# DR_EIB-128_MillMax_NewParts.net
KiCad netlist of a schematic drawn in EAGLE
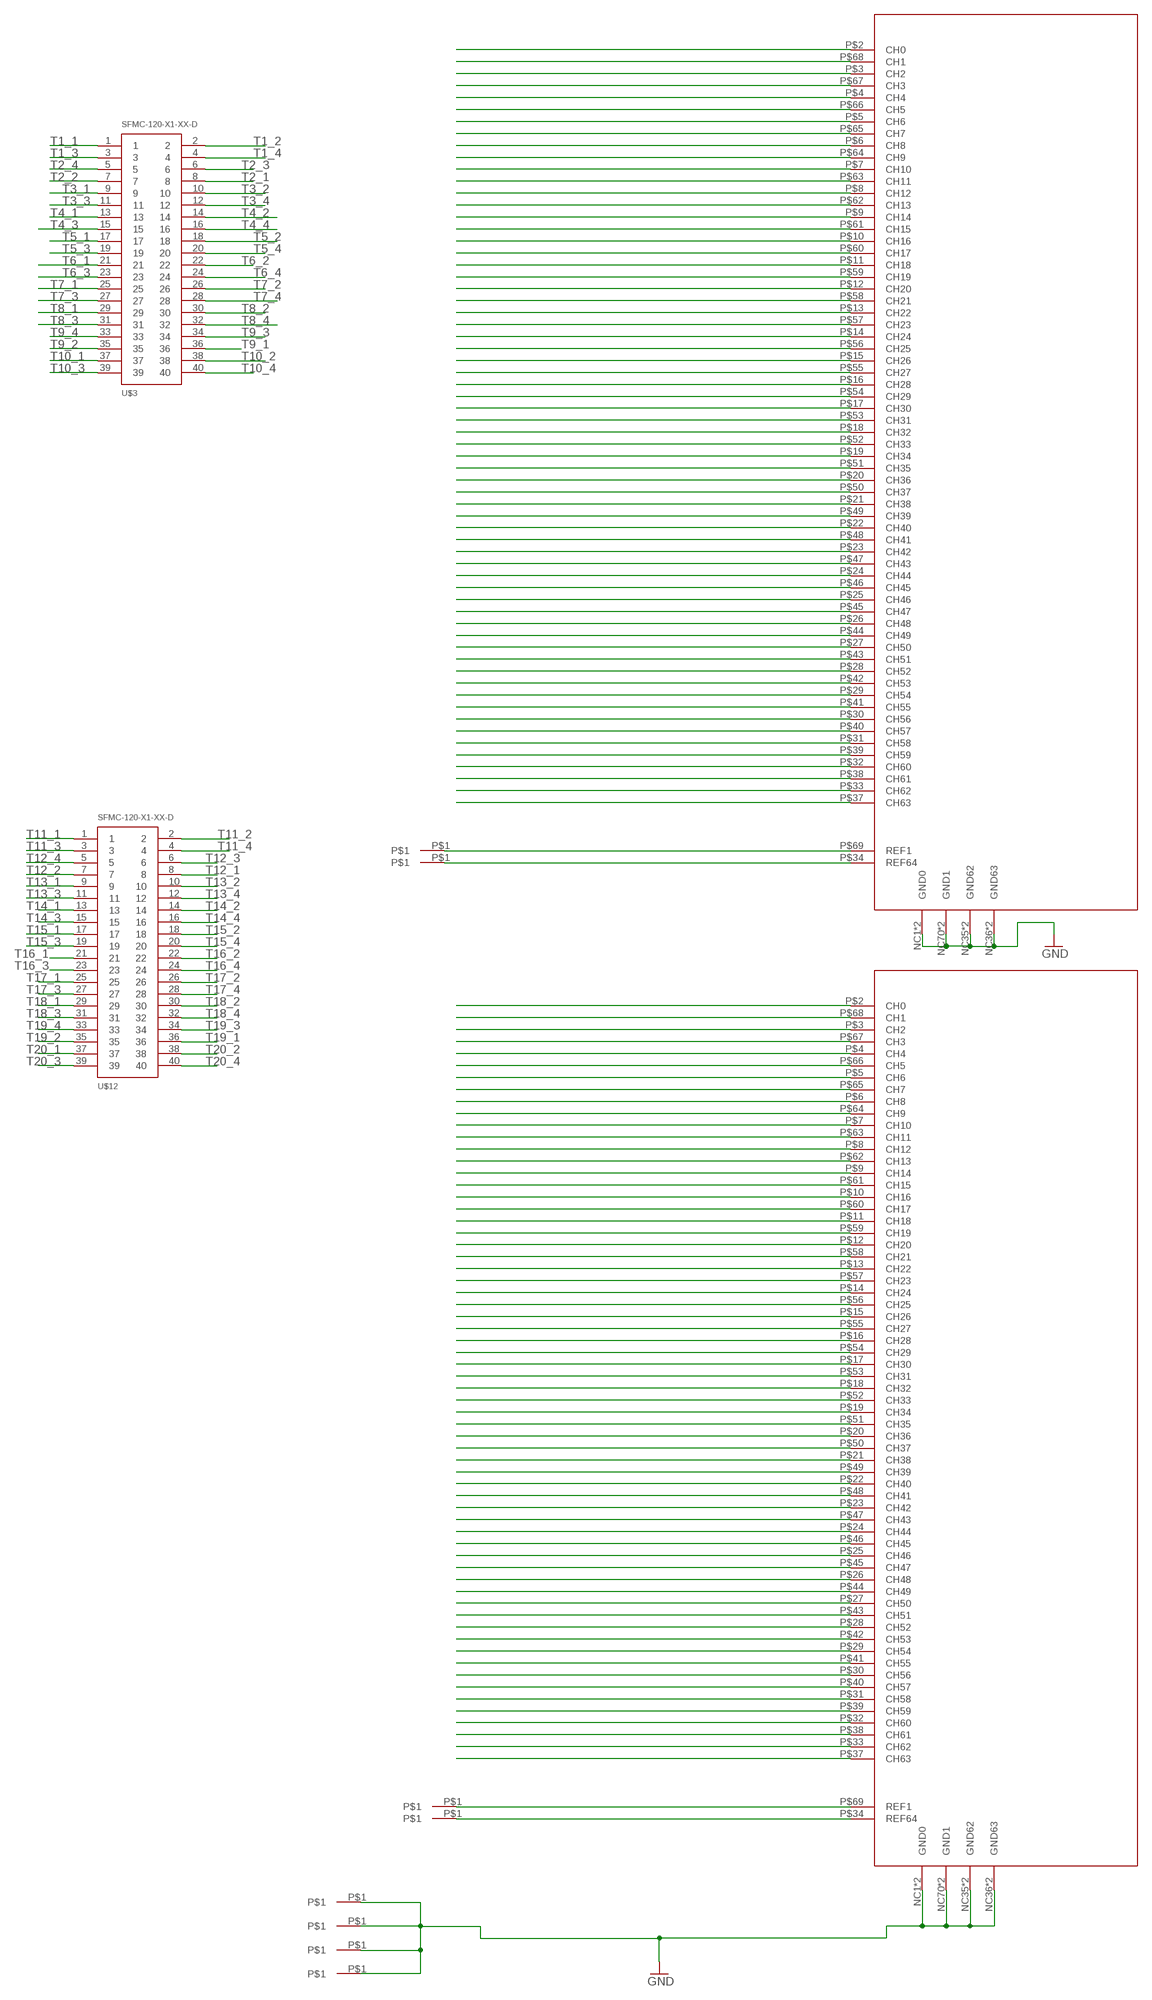
[diagram p0: schematic, sheet 1]

(export (version "E")
  (design (tool "Eeschema 10.0.6"))
  (components
    (comp (ref "U$1")
      (value "TARRAYSHUTTLEHOLE")
      (footprint "eagle-import:TARRAYSHUTTLEHOLE")
      (libsource (lib "eagle-import") (part "TARRAYSHUTTLEHOLE"))
    )
    (comp (ref "U$2")
      (value "TARRAYSHUTTLEHOLE")
      (footprint "eagle-import:TARRAYSHUTTLEHOLE")
      (libsource (lib "eagle-import") (part "TARRAYSHUTTLEHOLE"))
    )
    (comp (ref "U$3")
      (value "SFMC-120-X1-XX-D")
      (footprint "eagle-import:SFMC-120-X1-XX-D")
      (libsource (lib "eagle-import") (part "SFMC-120-X1-XX-D"))
    )
    (comp (ref "U$4")
      (value "TARRAYSHUTTLEHOLE")
      (footprint "eagle-import:TARRAYSHUTTLEHOLE")
      (libsource (lib "eagle-import") (part "TARRAYSHUTTLEHOLE"))
    )
    (comp (ref "U$5")
      (value "TARRAYSHUTTLEHOLE")
      (footprint "eagle-import:TARRAYSHUTTLEHOLE")
      (libsource (lib "eagle-import") (part "TARRAYSHUTTLEHOLE"))
    )
    (comp (ref "U$6")
      (value "TARRAYSHUTTLEHOLE")
      (footprint "eagle-import:TARRAYSHUTTLEHOLE")
      (libsource (lib "eagle-import") (part "TARRAYSHUTTLEHOLE"))
    )
    (comp (ref "U$7")
      (value "TARRAYSHUTTLEHOLE")
      (footprint "eagle-import:TARRAYSHUTTLEHOLE")
      (libsource (lib "eagle-import") (part "TARRAYSHUTTLEHOLE"))
    )
    (comp (ref "U$8")
      (value "TARRAYSHUTTLEHOLE")
      (footprint "eagle-import:TARRAYSHUTTLEHOLE")
      (libsource (lib "eagle-import") (part "TARRAYSHUTTLEHOLE"))
    )
    (comp (ref "U$9")
      (value "TARRAYSHUTTLEHOLE")
      (footprint "eagle-import:TARRAYSHUTTLEHOLE")
      (libsource (lib "eagle-import") (part "TARRAYSHUTTLEHOLE"))
    )
    (comp (ref "U$10")
      (value "HIROSE-70PIN-HEADER")
      (footprint "eagle-import:DF40C-70DP-0.4V")
      (libsource (lib "eagle-import") (part "HIROSE-70PIN-HEADER"))
    )
    (comp (ref "U$11")
      (value "HIROSE-70PIN-HEADER")
      (footprint "eagle-import:DF40C-70DP-0.4V")
      (libsource (lib "eagle-import") (part "HIROSE-70PIN-HEADER"))
    )
    (comp (ref "U$12")
      (value "SFMC-120-X1-XX-D")
      (footprint "eagle-import:SFMC-120-X1-XX-D")
      (libsource (lib "eagle-import") (part "SFMC-120-X1-XX-D"))
    )
  )
  (nets
    (net (code "1") (name "/T1_1") (class "Default")
      (node (ref "U$10") (pin "P$37") (pinfunction "CH63_P$37") (pintype "input"))
      (node (ref "U$3") (pin "1") (pinfunction "1_1") (pintype "bidirectional"))
    )
    (net (code "2") (name "/T1_2") (class "Default")
      (node (ref "U$10") (pin "P$38") (pinfunction "CH61_P$38") (pintype "input"))
      (node (ref "U$3") (pin "2") (pinfunction "2_2") (pintype "bidirectional"))
    )
    (net (code "3") (name "/T1_3") (class "Default")
      (node (ref "U$10") (pin "P$39") (pinfunction "CH59_P$39") (pintype "input"))
      (node (ref "U$3") (pin "3") (pinfunction "3_3") (pintype "bidirectional"))
    )
    (net (code "4") (name "/T1_4") (class "Default")
      (node (ref "U$10") (pin "P$40") (pinfunction "CH57_P$40") (pintype "input"))
      (node (ref "U$3") (pin "4") (pinfunction "4_4") (pintype "bidirectional"))
    )
    (net (code "5") (name "/T2_1") (class "Default")
      (node (ref "U$10") (pin "P$30") (pinfunction "CH56_P$30") (pintype "input"))
      (node (ref "U$3") (pin "8") (pinfunction "8_8") (pintype "bidirectional"))
    )
    (net (code "6") (name "/T2_2") (class "Default")
      (node (ref "U$10") (pin "P$31") (pinfunction "CH58_P$31") (pintype "input"))
      (node (ref "U$3") (pin "7") (pinfunction "7_7") (pintype "bidirectional"))
    )
    (net (code "7") (name "/T2_3") (class "Default")
      (node (ref "U$10") (pin "P$32") (pinfunction "CH60_P$32") (pintype "input"))
      (node (ref "U$3") (pin "6") (pinfunction "6_6") (pintype "bidirectional"))
    )
    (net (code "8") (name "/T2_4") (class "Default")
      (node (ref "U$10") (pin "P$33") (pinfunction "CH62_P$33") (pintype "input"))
      (node (ref "U$3") (pin "5") (pinfunction "5_5") (pintype "bidirectional"))
    )
    (net (code "9") (name "/T3_1") (class "Default")
      (node (ref "U$10") (pin "P$29") (pinfunction "CH54_P$29") (pintype "input"))
      (node (ref "U$3") (pin "9") (pinfunction "9_9") (pintype "bidirectional"))
    )
    (net (code "10") (name "/T3_2") (class "Default")
      (node (ref "U$10") (pin "P$28") (pinfunction "CH52_P$28") (pintype "input"))
      (node (ref "U$3") (pin "10") (pinfunction "10_10") (pintype "bidirectional"))
    )
    (net (code "11") (name "/T3_3") (class "Default")
      (node (ref "U$10") (pin "P$27") (pinfunction "CH50_P$27") (pintype "input"))
      (node (ref "U$3") (pin "11") (pinfunction "11_11") (pintype "bidirectional"))
    )
    (net (code "12") (name "/T3_4") (class "Default")
      (node (ref "U$10") (pin "P$26") (pinfunction "CH48_P$26") (pintype "input"))
      (node (ref "U$3") (pin "12") (pinfunction "12_12") (pintype "bidirectional"))
    )
    (net (code "13") (name "/T4_1") (class "Default")
      (node (ref "U$10") (pin "P$25") (pinfunction "CH46_P$25") (pintype "input"))
      (node (ref "U$3") (pin "13") (pinfunction "13_13") (pintype "bidirectional"))
    )
    (net (code "14") (name "/T4_2") (class "Default")
      (node (ref "U$10") (pin "P$24") (pinfunction "CH44_P$24") (pintype "input"))
      (node (ref "U$3") (pin "14") (pinfunction "14_14") (pintype "bidirectional"))
    )
    (net (code "15") (name "/T4_3") (class "Default")
      (node (ref "U$10") (pin "P$23") (pinfunction "CH42_P$23") (pintype "input"))
      (node (ref "U$3") (pin "15") (pinfunction "15_15") (pintype "bidirectional"))
    )
    (net (code "16") (name "/T4_4") (class "Default")
      (node (ref "U$10") (pin "P$22") (pinfunction "CH40_P$22") (pintype "input"))
      (node (ref "U$3") (pin "16") (pinfunction "16_16") (pintype "bidirectional"))
    )
    (net (code "17") (name "/T5_1") (class "Default")
      (node (ref "U$10") (pin "P$21") (pinfunction "CH38_P$21") (pintype "input"))
      (node (ref "U$3") (pin "17") (pinfunction "17_17") (pintype "bidirectional"))
    )
    (net (code "18") (name "/T5_2") (class "Default")
      (node (ref "U$10") (pin "P$20") (pinfunction "CH36_P$20") (pintype "input"))
      (node (ref "U$3") (pin "18") (pinfunction "18_18") (pintype "bidirectional"))
    )
    (net (code "19") (name "/T5_3") (class "Default")
      (node (ref "U$10") (pin "P$19") (pinfunction "CH34_P$19") (pintype "input"))
      (node (ref "U$3") (pin "19") (pinfunction "19_19") (pintype "bidirectional"))
    )
    (net (code "20") (name "/T5_4") (class "Default")
      (node (ref "U$10") (pin "P$18") (pinfunction "CH32_P$18") (pintype "input"))
      (node (ref "U$3") (pin "20") (pinfunction "20_20") (pintype "bidirectional"))
    )
    (net (code "21") (name "/T6_1") (class "Default")
      (node (ref "U$11") (pin "P$17") (pinfunction "CH30_P$17") (pintype "input"))
      (node (ref "U$3") (pin "21") (pinfunction "21_21") (pintype "bidirectional"))
    )
    (net (code "22") (name "/T6_2") (class "Default")
      (node (ref "U$11") (pin "P$16") (pinfunction "CH28_P$16") (pintype "input"))
      (node (ref "U$3") (pin "22") (pinfunction "22_22") (pintype "bidirectional"))
    )
    (net (code "23") (name "/T6_3") (class "Default")
      (node (ref "U$11") (pin "P$15") (pinfunction "CH26_P$15") (pintype "input"))
      (node (ref "U$3") (pin "23") (pinfunction "23_23") (pintype "bidirectional"))
    )
    (net (code "24") (name "/T6_4") (class "Default")
      (node (ref "U$11") (pin "P$14") (pinfunction "CH24_P$14") (pintype "input"))
      (node (ref "U$3") (pin "24") (pinfunction "24_24") (pintype "bidirectional"))
    )
    (net (code "25") (name "/T7_1") (class "Default")
      (node (ref "U$11") (pin "P$13") (pinfunction "CH22_P$13") (pintype "input"))
      (node (ref "U$3") (pin "25") (pinfunction "25_25") (pintype "bidirectional"))
    )
    (net (code "26") (name "/T7_2") (class "Default")
      (node (ref "U$11") (pin "P$12") (pinfunction "CH20_P$12") (pintype "input"))
      (node (ref "U$3") (pin "26") (pinfunction "26_26") (pintype "bidirectional"))
    )
    (net (code "27") (name "/T7_3") (class "Default")
      (node (ref "U$11") (pin "P$11") (pinfunction "CH18_P$11") (pintype "input"))
      (node (ref "U$3") (pin "27") (pinfunction "27_27") (pintype "bidirectional"))
    )
    (net (code "28") (name "/T7_4") (class "Default")
      (node (ref "U$11") (pin "P$10") (pinfunction "CH16_P$10") (pintype "input"))
      (node (ref "U$3") (pin "28") (pinfunction "28_28") (pintype "bidirectional"))
    )
    (net (code "29") (name "/T8_1") (class "Default")
      (node (ref "U$11") (pin "P$9") (pinfunction "CH14_P$9") (pintype "input"))
      (node (ref "U$3") (pin "29") (pinfunction "29_29") (pintype "bidirectional"))
    )
    (net (code "30") (name "/T8_2") (class "Default")
      (node (ref "U$11") (pin "P$8") (pinfunction "CH12_P$8") (pintype "input"))
      (node (ref "U$3") (pin "30") (pinfunction "30_30") (pintype "bidirectional"))
    )
    (net (code "31") (name "/T8_3") (class "Default")
      (node (ref "U$11") (pin "P$7") (pinfunction "CH10_P$7") (pintype "input"))
      (node (ref "U$3") (pin "31") (pinfunction "31_31") (pintype "bidirectional"))
    )
    (net (code "32") (name "/T8_4") (class "Default")
      (node (ref "U$11") (pin "P$6") (pinfunction "CH8_P$6") (pintype "input"))
      (node (ref "U$3") (pin "32") (pinfunction "32_32") (pintype "bidirectional"))
    )
    (net (code "33") (name "/T9_1") (class "Default")
      (node (ref "U$11") (pin "P$2") (pinfunction "CH0_P$2") (pintype "input"))
      (node (ref "U$3") (pin "36") (pinfunction "36_36") (pintype "bidirectional"))
    )
    (net (code "34") (name "/T9_2") (class "Default")
      (node (ref "U$11") (pin "P$3") (pinfunction "CH2_P$3") (pintype "input"))
      (node (ref "U$3") (pin "35") (pinfunction "35_35") (pintype "bidirectional"))
    )
    (net (code "35") (name "/T9_3") (class "Default")
      (node (ref "U$11") (pin "P$4") (pinfunction "CH4_P$4") (pintype "input"))
      (node (ref "U$3") (pin "34") (pinfunction "34_34") (pintype "bidirectional"))
    )
    (net (code "36") (name "/T9_4") (class "Default")
      (node (ref "U$11") (pin "P$5") (pinfunction "CH6_P$5") (pintype "input"))
      (node (ref "U$3") (pin "33") (pinfunction "33_33") (pintype "bidirectional"))
    )
    (net (code "37") (name "/T10_1") (class "Default")
      (node (ref "U$11") (pin "P$65") (pinfunction "CH7_P$65") (pintype "input"))
      (node (ref "U$3") (pin "37") (pinfunction "37_37") (pintype "bidirectional"))
    )
    (net (code "38") (name "/T10_2") (class "Default")
      (node (ref "U$11") (pin "P$66") (pinfunction "CH5_P$66") (pintype "input"))
      (node (ref "U$3") (pin "38") (pinfunction "38_38") (pintype "bidirectional"))
    )
    (net (code "39") (name "/T10_3") (class "Default")
      (node (ref "U$11") (pin "P$67") (pinfunction "CH3_P$67") (pintype "input"))
      (node (ref "U$3") (pin "39") (pinfunction "39_39") (pintype "bidirectional"))
    )
    (net (code "40") (name "/T10_4") (class "Default")
      (node (ref "U$11") (pin "P$68") (pinfunction "CH1_P$68") (pintype "input"))
      (node (ref "U$3") (pin "40") (pinfunction "40_40") (pintype "bidirectional"))
    )
    (net (code "41") (name "/T11_1") (class "Default")
      (node (ref "U$11") (pin "P$37") (pinfunction "CH63_P$37") (pintype "input"))
      (node (ref "U$12") (pin "1") (pinfunction "1_1") (pintype "bidirectional"))
    )
    (net (code "42") (name "/T11_2") (class "Default")
      (node (ref "U$11") (pin "P$38") (pinfunction "CH61_P$38") (pintype "input"))
      (node (ref "U$12") (pin "2") (pinfunction "2_2") (pintype "bidirectional"))
    )
    (net (code "43") (name "/T11_3") (class "Default")
      (node (ref "U$11") (pin "P$39") (pinfunction "CH59_P$39") (pintype "input"))
      (node (ref "U$12") (pin "3") (pinfunction "3_3") (pintype "bidirectional"))
    )
    (net (code "44") (name "/T11_4") (class "Default")
      (node (ref "U$11") (pin "P$40") (pinfunction "CH57_P$40") (pintype "input"))
      (node (ref "U$12") (pin "4") (pinfunction "4_4") (pintype "bidirectional"))
    )
    (net (code "45") (name "/T12_1") (class "Default")
      (node (ref "U$11") (pin "P$30") (pinfunction "CH56_P$30") (pintype "input"))
      (node (ref "U$12") (pin "8") (pinfunction "8_8") (pintype "bidirectional"))
    )
    (net (code "46") (name "/T12_2") (class "Default")
      (node (ref "U$11") (pin "P$31") (pinfunction "CH58_P$31") (pintype "input"))
      (node (ref "U$12") (pin "7") (pinfunction "7_7") (pintype "bidirectional"))
    )
    (net (code "47") (name "/T12_3") (class "Default")
      (node (ref "U$11") (pin "P$32") (pinfunction "CH60_P$32") (pintype "input"))
      (node (ref "U$12") (pin "6") (pinfunction "6_6") (pintype "bidirectional"))
    )
    (net (code "48") (name "/T12_4") (class "Default")
      (node (ref "U$11") (pin "P$33") (pinfunction "CH62_P$33") (pintype "input"))
      (node (ref "U$12") (pin "5") (pinfunction "5_5") (pintype "bidirectional"))
    )
    (net (code "49") (name "/T13_1") (class "Default")
      (node (ref "U$11") (pin "P$29") (pinfunction "CH54_P$29") (pintype "input"))
      (node (ref "U$12") (pin "9") (pinfunction "9_9") (pintype "bidirectional"))
    )
    (net (code "50") (name "/T13_2") (class "Default")
      (node (ref "U$11") (pin "P$28") (pinfunction "CH52_P$28") (pintype "input"))
      (node (ref "U$12") (pin "10") (pinfunction "10_10") (pintype "bidirectional"))
    )
    (net (code "51") (name "/T13_3") (class "Default")
      (node (ref "U$11") (pin "P$27") (pinfunction "CH50_P$27") (pintype "input"))
      (node (ref "U$12") (pin "11") (pinfunction "11_11") (pintype "bidirectional"))
    )
    (net (code "52") (name "/T13_4") (class "Default")
      (node (ref "U$11") (pin "P$26") (pinfunction "CH48_P$26") (pintype "input"))
      (node (ref "U$12") (pin "12") (pinfunction "12_12") (pintype "bidirectional"))
    )
    (net (code "53") (name "/T14_1") (class "Default")
      (node (ref "U$11") (pin "P$25") (pinfunction "CH46_P$25") (pintype "input"))
      (node (ref "U$12") (pin "13") (pinfunction "13_13") (pintype "bidirectional"))
    )
    (net (code "54") (name "/T14_2") (class "Default")
      (node (ref "U$11") (pin "P$24") (pinfunction "CH44_P$24") (pintype "input"))
      (node (ref "U$12") (pin "14") (pinfunction "14_14") (pintype "bidirectional"))
    )
    (net (code "55") (name "/T14_3") (class "Default")
      (node (ref "U$11") (pin "P$23") (pinfunction "CH42_P$23") (pintype "input"))
      (node (ref "U$12") (pin "15") (pinfunction "15_15") (pintype "bidirectional"))
    )
    (net (code "56") (name "/T14_4") (class "Default")
      (node (ref "U$11") (pin "P$22") (pinfunction "CH40_P$22") (pintype "input"))
      (node (ref "U$12") (pin "16") (pinfunction "16_16") (pintype "bidirectional"))
    )
    (net (code "57") (name "/T15_1") (class "Default")
      (node (ref "U$11") (pin "P$21") (pinfunction "CH38_P$21") (pintype "input"))
      (node (ref "U$12") (pin "17") (pinfunction "17_17") (pintype "bidirectional"))
    )
    (net (code "58") (name "/T15_2") (class "Default")
      (node (ref "U$11") (pin "P$20") (pinfunction "CH36_P$20") (pintype "input"))
      (node (ref "U$12") (pin "18") (pinfunction "18_18") (pintype "bidirectional"))
    )
    (net (code "59") (name "/T15_3") (class "Default")
      (node (ref "U$11") (pin "P$19") (pinfunction "CH34_P$19") (pintype "input"))
      (node (ref "U$12") (pin "19") (pinfunction "19_19") (pintype "bidirectional"))
    )
    (net (code "60") (name "/T15_4") (class "Default")
      (node (ref "U$11") (pin "P$18") (pinfunction "CH32_P$18") (pintype "input"))
      (node (ref "U$12") (pin "20") (pinfunction "20_20") (pintype "bidirectional"))
    )
    (net (code "61") (name "/T16_1") (class "Default")
      (node (ref "U$10") (pin "P$17") (pinfunction "CH30_P$17") (pintype "input"))
      (node (ref "U$12") (pin "21") (pinfunction "21_21") (pintype "bidirectional"))
    )
    (net (code "62") (name "/T16_2") (class "Default")
      (node (ref "U$10") (pin "P$16") (pinfunction "CH28_P$16") (pintype "input"))
      (node (ref "U$12") (pin "22") (pinfunction "22_22") (pintype "bidirectional"))
    )
    (net (code "63") (name "/T16_3") (class "Default")
      (node (ref "U$10") (pin "P$15") (pinfunction "CH26_P$15") (pintype "input"))
      (node (ref "U$12") (pin "23") (pinfunction "23_23") (pintype "bidirectional"))
    )
    (net (code "64") (name "/T16_4") (class "Default")
      (node (ref "U$10") (pin "P$14") (pinfunction "CH24_P$14") (pintype "input"))
      (node (ref "U$12") (pin "24") (pinfunction "24_24") (pintype "bidirectional"))
    )
    (net (code "65") (name "/T17_1") (class "Default")
      (node (ref "U$10") (pin "P$13") (pinfunction "CH22_P$13") (pintype "input"))
      (node (ref "U$12") (pin "25") (pinfunction "25_25") (pintype "bidirectional"))
    )
    (net (code "66") (name "/T17_2") (class "Default")
      (node (ref "U$10") (pin "P$12") (pinfunction "CH20_P$12") (pintype "input"))
      (node (ref "U$12") (pin "26") (pinfunction "26_26") (pintype "bidirectional"))
    )
    (net (code "67") (name "/T17_3") (class "Default")
      (node (ref "U$10") (pin "P$11") (pinfunction "CH18_P$11") (pintype "input"))
      (node (ref "U$12") (pin "27") (pinfunction "27_27") (pintype "bidirectional"))
    )
    (net (code "68") (name "/T17_4") (class "Default")
      (node (ref "U$10") (pin "P$10") (pinfunction "CH16_P$10") (pintype "input"))
      (node (ref "U$12") (pin "28") (pinfunction "28_28") (pintype "bidirectional"))
    )
    (net (code "69") (name "/T18_1") (class "Default")
      (node (ref "U$10") (pin "P$9") (pinfunction "CH14_P$9") (pintype "input"))
      (node (ref "U$12") (pin "29") (pinfunction "29_29") (pintype "bidirectional"))
    )
    (net (code "70") (name "/T18_2") (class "Default")
      (node (ref "U$10") (pin "P$8") (pinfunction "CH12_P$8") (pintype "input"))
      (node (ref "U$12") (pin "30") (pinfunction "30_30") (pintype "bidirectional"))
    )
    (net (code "71") (name "/T18_3") (class "Default")
      (node (ref "U$10") (pin "P$7") (pinfunction "CH10_P$7") (pintype "input"))
      (node (ref "U$12") (pin "31") (pinfunction "31_31") (pintype "bidirectional"))
    )
    (net (code "72") (name "/T18_4") (class "Default")
      (node (ref "U$10") (pin "P$6") (pinfunction "CH8_P$6") (pintype "input"))
      (node (ref "U$12") (pin "32") (pinfunction "32_32") (pintype "bidirectional"))
    )
    (net (code "73") (name "/T19_1") (class "Default")
      (node (ref "U$10") (pin "P$2") (pinfunction "CH0_P$2") (pintype "input"))
      (node (ref "U$12") (pin "36") (pinfunction "36_36") (pintype "bidirectional"))
    )
    (net (code "74") (name "/T19_2") (class "Default")
      (node (ref "U$10") (pin "P$3") (pinfunction "CH2_P$3") (pintype "input"))
      (node (ref "U$12") (pin "35") (pinfunction "35_35") (pintype "bidirectional"))
    )
    (net (code "75") (name "/T19_3") (class "Default")
      (node (ref "U$10") (pin "P$4") (pinfunction "CH4_P$4") (pintype "input"))
      (node (ref "U$12") (pin "34") (pinfunction "34_34") (pintype "bidirectional"))
    )
    (net (code "76") (name "/T19_4") (class "Default")
      (node (ref "U$10") (pin "P$5") (pinfunction "CH6_P$5") (pintype "input"))
      (node (ref "U$12") (pin "33") (pinfunction "33_33") (pintype "bidirectional"))
    )
    (net (code "77") (name "/T20_1") (class "Default")
      (node (ref "U$10") (pin "P$65") (pinfunction "CH7_P$65") (pintype "input"))
      (node (ref "U$12") (pin "37") (pinfunction "37_37") (pintype "bidirectional"))
    )
    (net (code "78") (name "/T20_2") (class "Default")
      (node (ref "U$10") (pin "P$66") (pinfunction "CH5_P$66") (pintype "input"))
      (node (ref "U$12") (pin "38") (pinfunction "38_38") (pintype "bidirectional"))
    )
    (net (code "79") (name "/T20_3") (class "Default")
      (node (ref "U$10") (pin "P$67") (pinfunction "CH3_P$67") (pintype "input"))
      (node (ref "U$12") (pin "39") (pinfunction "39_39") (pintype "bidirectional"))
    )
    (net (code "80") (name "/T20_4") (class "Default")
      (node (ref "U$10") (pin "P$68") (pinfunction "CH1_P$68") (pintype "input"))
      (node (ref "U$12") (pin "40") (pinfunction "40_40") (pintype "bidirectional"))
    )
    (net (code "81") (name "GND") (class "Default")
      (node (ref "U$1") (pin "P$1") (pinfunction "P$1_P$1") (pintype "bidirectional"))
      (node (ref "U$10") (pin "NC1") (pinfunction "GND0_NC1") (pintype "power_in"))
      (node (ref "U$10") (pin "NC35") (pinfunction "GND62_NC35") (pintype "power_in"))
      (node (ref "U$10") (pin "NC36") (pinfunction "GND63_NC36") (pintype "power_in"))
      (node (ref "U$10") (pin "NC70") (pinfunction "GND1_NC70") (pintype "power_in"))
      (node (ref "U$10") (pin "P$1") (pinfunction "GND0_P$1") (pintype "power_in"))
      (node (ref "U$10") (pin "P$35") (pinfunction "GND62_P$35") (pintype "power_in"))
      (node (ref "U$10") (pin "P$36") (pinfunction "GND63_P$36") (pintype "power_in"))
      (node (ref "U$10") (pin "P$70") (pinfunction "GND1_P$70") (pintype "power_in"))
      (node (ref "U$11") (pin "NC1") (pinfunction "GND0_NC1") (pintype "power_in"))
      (node (ref "U$11") (pin "NC35") (pinfunction "GND62_NC35") (pintype "power_in"))
      (node (ref "U$11") (pin "NC36") (pinfunction "GND63_NC36") (pintype "power_in"))
      (node (ref "U$11") (pin "NC70") (pinfunction "GND1_NC70") (pintype "power_in"))
      (node (ref "U$11") (pin "P$1") (pinfunction "GND0_P$1") (pintype "power_in"))
      (node (ref "U$11") (pin "P$35") (pinfunction "GND62_P$35") (pintype "power_in"))
      (node (ref "U$11") (pin "P$36") (pinfunction "GND63_P$36") (pintype "power_in"))
      (node (ref "U$11") (pin "P$70") (pinfunction "GND1_P$70") (pintype "power_in"))
      (node (ref "U$2") (pin "P$1") (pinfunction "P$1_P$1") (pintype "bidirectional"))
      (node (ref "U$4") (pin "P$1") (pinfunction "P$1_P$1") (pintype "bidirectional"))
      (node (ref "U$5") (pin "P$1") (pinfunction "P$1_P$1") (pintype "bidirectional"))
    )
    (net (code "82") (name "Net-(U$10-REF1)") (class "Default")
      (node (ref "U$10") (pin "P$69") (pinfunction "REF1_P$69") (pintype "input"))
      (node (ref "U$7") (pin "P$1") (pinfunction "P$1_P$1") (pintype "bidirectional"))
    )
    (net (code "83") (name "Net-(U$10-REF64)") (class "Default")
      (node (ref "U$10") (pin "P$34") (pinfunction "REF64_P$34") (pintype "input"))
      (node (ref "U$6") (pin "P$1") (pinfunction "P$1_P$1") (pintype "bidirectional"))
    )
    (net (code "84") (name "Net-(U$11-REF1)") (class "Default")
      (node (ref "U$11") (pin "P$69") (pinfunction "REF1_P$69") (pintype "input"))
      (node (ref "U$9") (pin "P$1") (pinfunction "P$1_P$1") (pintype "bidirectional"))
    )
    (net (code "85") (name "Net-(U$11-REF64)") (class "Default")
      (node (ref "U$11") (pin "P$34") (pinfunction "REF64_P$34") (pintype "input"))
      (node (ref "U$8") (pin "P$1") (pinfunction "P$1_P$1") (pintype "bidirectional"))
    )
    (net (code "86") (name "unconnected-(U$10-CH9-PadP$64)") (class "Default")
      (node (ref "U$10") (pin "P$64") (pinfunction "CH9_P$64") (pintype "input"))
    )
    (net (code "87") (name "unconnected-(U$10-CH11-PadP$63)") (class "Default")
      (node (ref "U$10") (pin "P$63") (pinfunction "CH11_P$63") (pintype "input"))
    )
    (net (code "88") (name "unconnected-(U$10-CH13-PadP$62)") (class "Default")
      (node (ref "U$10") (pin "P$62") (pinfunction "CH13_P$62") (pintype "input"))
    )
    (net (code "89") (name "unconnected-(U$10-CH15-PadP$61)") (class "Default")
      (node (ref "U$10") (pin "P$61") (pinfunction "CH15_P$61") (pintype "input"))
    )
    (net (code "90") (name "unconnected-(U$10-CH17-PadP$60)") (class "Default")
      (node (ref "U$10") (pin "P$60") (pinfunction "CH17_P$60") (pintype "input"))
    )
    (net (code "91") (name "unconnected-(U$10-CH19-PadP$59)") (class "Default")
      (node (ref "U$10") (pin "P$59") (pinfunction "CH19_P$59") (pintype "input"))
    )
    (net (code "92") (name "unconnected-(U$10-CH21-PadP$58)") (class "Default")
      (node (ref "U$10") (pin "P$58") (pinfunction "CH21_P$58") (pintype "input"))
    )
    (net (code "93") (name "unconnected-(U$10-CH23-PadP$57)") (class "Default")
      (node (ref "U$10") (pin "P$57") (pinfunction "CH23_P$57") (pintype "input"))
    )
    (net (code "94") (name "unconnected-(U$10-CH25-PadP$56)") (class "Default")
      (node (ref "U$10") (pin "P$56") (pinfunction "CH25_P$56") (pintype "input"))
    )
    (net (code "95") (name "unconnected-(U$10-CH27-PadP$55)") (class "Default")
      (node (ref "U$10") (pin "P$55") (pinfunction "CH27_P$55") (pintype "input"))
    )
    (net (code "96") (name "unconnected-(U$10-CH29-PadP$54)") (class "Default")
      (node (ref "U$10") (pin "P$54") (pinfunction "CH29_P$54") (pintype "input"))
    )
    (net (code "97") (name "unconnected-(U$10-CH31-PadP$53)") (class "Default")
      (node (ref "U$10") (pin "P$53") (pinfunction "CH31_P$53") (pintype "input"))
    )
    (net (code "98") (name "unconnected-(U$10-CH33-PadP$52)") (class "Default")
      (node (ref "U$10") (pin "P$52") (pinfunction "CH33_P$52") (pintype "input"))
    )
    (net (code "99") (name "unconnected-(U$10-CH35-PadP$51)") (class "Default")
      (node (ref "U$10") (pin "P$51") (pinfunction "CH35_P$51") (pintype "input"))
    )
    (net (code "100") (name "unconnected-(U$10-CH37-PadP$50)") (class "Default")
      (node (ref "U$10") (pin "P$50") (pinfunction "CH37_P$50") (pintype "input"))
    )
    (net (code "101") (name "unconnected-(U$10-CH39-PadP$49)") (class "Default")
      (node (ref "U$10") (pin "P$49") (pinfunction "CH39_P$49") (pintype "input"))
    )
    (net (code "102") (name "unconnected-(U$10-CH41-PadP$48)") (class "Default")
      (node (ref "U$10") (pin "P$48") (pinfunction "CH41_P$48") (pintype "input"))
    )
    (net (code "103") (name "unconnected-(U$10-CH43-PadP$47)") (class "Default")
      (node (ref "U$10") (pin "P$47") (pinfunction "CH43_P$47") (pintype "input"))
    )
    (net (code "104") (name "unconnected-(U$10-CH45-PadP$46)") (class "Default")
      (node (ref "U$10") (pin "P$46") (pinfunction "CH45_P$46") (pintype "input"))
    )
    (net (code "105") (name "unconnected-(U$10-CH47-PadP$45)") (class "Default")
      (node (ref "U$10") (pin "P$45") (pinfunction "CH47_P$45") (pintype "input"))
    )
    (net (code "106") (name "unconnected-(U$10-CH49-PadP$44)") (class "Default")
      (node (ref "U$10") (pin "P$44") (pinfunction "CH49_P$44") (pintype "input"))
    )
    (net (code "107") (name "unconnected-(U$10-CH51-PadP$43)") (class "Default")
      (node (ref "U$10") (pin "P$43") (pinfunction "CH51_P$43") (pintype "input"))
    )
    (net (code "108") (name "unconnected-(U$10-CH53-PadP$42)") (class "Default")
      (node (ref "U$10") (pin "P$42") (pinfunction "CH53_P$42") (pintype "input"))
    )
    (net (code "109") (name "unconnected-(U$10-CH55-PadP$41)") (class "Default")
      (node (ref "U$10") (pin "P$41") (pinfunction "CH55_P$41") (pintype "input"))
    )
    (net (code "110") (name "unconnected-(U$11-CH9-PadP$64)") (class "Default")
      (node (ref "U$11") (pin "P$64") (pinfunction "CH9_P$64") (pintype "input"))
    )
    (net (code "111") (name "unconnected-(U$11-CH11-PadP$63)") (class "Default")
      (node (ref "U$11") (pin "P$63") (pinfunction "CH11_P$63") (pintype "input"))
    )
    (net (code "112") (name "unconnected-(U$11-CH13-PadP$62)") (class "Default")
      (node (ref "U$11") (pin "P$62") (pinfunction "CH13_P$62") (pintype "input"))
    )
    (net (code "113") (name "unconnected-(U$11-CH15-PadP$61)") (class "Default")
      (node (ref "U$11") (pin "P$61") (pinfunction "CH15_P$61") (pintype "input"))
    )
    (net (code "114") (name "unconnected-(U$11-CH17-PadP$60)") (class "Default")
      (node (ref "U$11") (pin "P$60") (pinfunction "CH17_P$60") (pintype "input"))
    )
    (net (code "115") (name "unconnected-(U$11-CH19-PadP$59)") (class "Default")
      (node (ref "U$11") (pin "P$59") (pinfunction "CH19_P$59") (pintype "input"))
    )
    (net (code "116") (name "unconnected-(U$11-CH21-PadP$58)") (class "Default")
      (node (ref "U$11") (pin "P$58") (pinfunction "CH21_P$58") (pintype "input"))
    )
    (net (code "117") (name "unconnected-(U$11-CH23-PadP$57)") (class "Default")
      (node (ref "U$11") (pin "P$57") (pinfunction "CH23_P$57") (pintype "input"))
    )
    (net (code "118") (name "unconnected-(U$11-CH25-PadP$56)") (class "Default")
      (node (ref "U$11") (pin "P$56") (pinfunction "CH25_P$56") (pintype "input"))
    )
    (net (code "119") (name "unconnected-(U$11-CH27-PadP$55)") (class "Default")
      (node (ref "U$11") (pin "P$55") (pinfunction "CH27_P$55") (pintype "input"))
    )
    (net (code "120") (name "unconnected-(U$11-CH29-PadP$54)") (class "Default")
      (node (ref "U$11") (pin "P$54") (pinfunction "CH29_P$54") (pintype "input"))
    )
    (net (code "121") (name "unconnected-(U$11-CH31-PadP$53)") (class "Default")
      (node (ref "U$11") (pin "P$53") (pinfunction "CH31_P$53") (pintype "input"))
    )
    (net (code "122") (name "unconnected-(U$11-CH33-PadP$52)") (class "Default")
      (node (ref "U$11") (pin "P$52") (pinfunction "CH33_P$52") (pintype "input"))
    )
    (net (code "123") (name "unconnected-(U$11-CH35-PadP$51)") (class "Default")
      (node (ref "U$11") (pin "P$51") (pinfunction "CH35_P$51") (pintype "input"))
    )
    (net (code "124") (name "unconnected-(U$11-CH37-PadP$50)") (class "Default")
      (node (ref "U$11") (pin "P$50") (pinfunction "CH37_P$50") (pintype "input"))
    )
    (net (code "125") (name "unconnected-(U$11-CH39-PadP$49)") (class "Default")
      (node (ref "U$11") (pin "P$49") (pinfunction "CH39_P$49") (pintype "input"))
    )
    (net (code "126") (name "unconnected-(U$11-CH41-PadP$48)") (class "Default")
      (node (ref "U$11") (pin "P$48") (pinfunction "CH41_P$48") (pintype "input"))
    )
    (net (code "127") (name "unconnected-(U$11-CH43-PadP$47)") (class "Default")
      (node (ref "U$11") (pin "P$47") (pinfunction "CH43_P$47") (pintype "input"))
    )
    (net (code "128") (name "unconnected-(U$11-CH45-PadP$46)") (class "Default")
      (node (ref "U$11") (pin "P$46") (pinfunction "CH45_P$46") (pintype "input"))
    )
    (net (code "129") (name "unconnected-(U$11-CH47-PadP$45)") (class "Default")
      (node (ref "U$11") (pin "P$45") (pinfunction "CH47_P$45") (pintype "input"))
    )
    (net (code "130") (name "unconnected-(U$11-CH49-PadP$44)") (class "Default")
      (node (ref "U$11") (pin "P$44") (pinfunction "CH49_P$44") (pintype "input"))
    )
    (net (code "131") (name "unconnected-(U$11-CH51-PadP$43)") (class "Default")
      (node (ref "U$11") (pin "P$43") (pinfunction "CH51_P$43") (pintype "input"))
    )
    (net (code "132") (name "unconnected-(U$11-CH53-PadP$42)") (class "Default")
      (node (ref "U$11") (pin "P$42") (pinfunction "CH53_P$42") (pintype "input"))
    )
    (net (code "133") (name "unconnected-(U$11-CH55-PadP$41)") (class "Default")
      (node (ref "U$11") (pin "P$41") (pinfunction "CH55_P$41") (pintype "input"))
    )
  )
)
